# Ref_Volt.net
KiCad netlist of a schematic drawn in Altium Designer
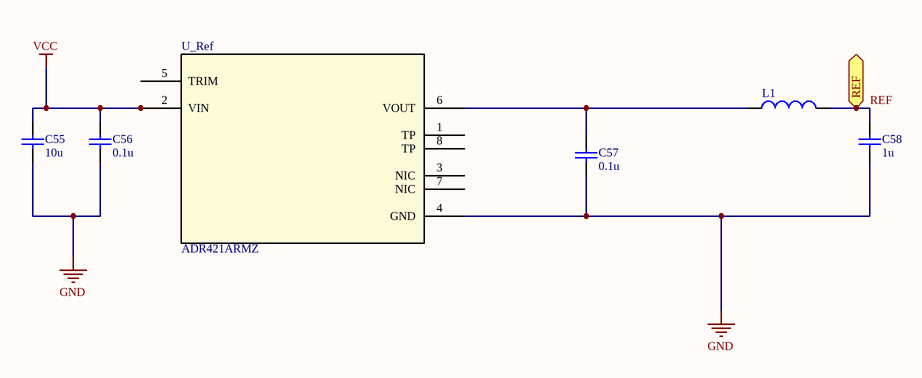
[diagram p0: Ref Volt.SchDoc]

(export (version "E")
  (design (tool "Eeschema 10.0.6"))
  (components
    (comp (ref "C55")
      (value "10u")
      (footprint "0805")
      (description "Ceramic Chip Capacitor - Standard")
      (fields (field (name "Comment") "C0805") (field (name "PUBLISHER") "Altium Limited"))
      (libsource (lib "KEMET Chip Capacitor") (part "C0805"))
    )
    (comp (ref "C56")
      (value "0.1u")
      (footprint "0603")
      (description "Ceramic Chip Capacitor - Standard")
      (fields (field (name "Comment") "C0603") (field (name "PUBLISHER") "Altium Limited"))
      (libsource (lib "KEMET Chip Capacitor") (part "C0603"))
    )
    (comp (ref "C57")
      (value "0.1u")
      (footprint "0603")
      (description "Ceramic Chip Capacitor - Standard")
      (fields (field (name "Comment") "C0603") (field (name "PUBLISHER") "Altium Limited"))
      (libsource (lib "KEMET Chip Capacitor") (part "C0603"))
    )
    (comp (ref "C58")
      (value "1u")
      (footprint "0805")
      (description "Ceramic Chip Capacitor - Standard")
      (fields (field (name "Comment") "C0805") (field (name "PUBLISHER") "Altium Limited"))
      (libsource (lib "KEMET Chip Capacitor") (part "C0805"))
    )
    (comp (ref "L1")
      (value "Inductor")
      (footprint "INDC1608L")
      (fields (field (name "PUBLISHER") "Altium Limited"))
      (libsource (lib "Miscellaneous Devices") (part "Inductor"))
    )
    (comp (ref "U_Ref")
      (value "ADR421ARMZ")
      (footprint "RM_8")
      (description "Imported")
      (libsource (lib "2016-11-05_23-52-08") (part "ADR421ARMZ"))
    )
  )
  (nets
    (net (code "1") (name "/REF") (class "Default")
      (node (ref "C58") (pin "1") (pinfunction "1_1") (pintype "passive"))
      (node (ref "L1") (pin "2") (pinfunction "2_2") (pintype "passive"))
    )
    (net (code "2") (name "GND") (class "Default")
      (node (ref "C55") (pin "1") (pinfunction "1_1") (pintype "passive"))
      (node (ref "C56") (pin "1") (pinfunction "1_1") (pintype "passive"))
      (node (ref "C57") (pin "1") (pinfunction "1_1") (pintype "passive"))
      (node (ref "C58") (pin "2") (pinfunction "2_2") (pintype "passive"))
      (node (ref "U_Ref") (pin "4") (pinfunction "GND_4") (pintype "passive"))
    )
    (net (code "3") (name "Net-(U_Ref-VOUT)") (class "Default")
      (node (ref "C57") (pin "2") (pinfunction "2_2") (pintype "passive"))
      (node (ref "L1") (pin "1") (pinfunction "1_1") (pintype "passive"))
      (node (ref "U_Ref") (pin "6") (pinfunction "VOUT_6") (pintype "passive"))
    )
    (net (code "4") (name "VCC") (class "Default")
      (node (ref "C55") (pin "2") (pinfunction "2_2") (pintype "passive"))
      (node (ref "C56") (pin "2") (pinfunction "2_2") (pintype "passive"))
      (node (ref "U_Ref") (pin "2") (pinfunction "VIN_2") (pintype "passive"))
    )
    (net (code "5") (name "unconnected-(U_Ref-NIC-Pad3)") (class "Default")
      (node (ref "U_Ref") (pin "3") (pinfunction "NIC_3") (pintype "passive"))
    )
    (net (code "6") (name "unconnected-(U_Ref-NIC-Pad7)") (class "Default")
      (node (ref "U_Ref") (pin "7") (pinfunction "NIC_7") (pintype "passive"))
    )
    (net (code "7") (name "unconnected-(U_Ref-TP-Pad1)") (class "Default")
      (node (ref "U_Ref") (pin "1") (pinfunction "TP_1") (pintype "passive"))
    )
    (net (code "8") (name "unconnected-(U_Ref-TP-Pad8)") (class "Default")
      (node (ref "U_Ref") (pin "8") (pinfunction "TP_8") (pintype "passive"))
    )
    (net (code "9") (name "unconnected-(U_Ref-TRIM-Pad5)") (class "Default")
      (node (ref "U_Ref") (pin "5") (pinfunction "TRIM_5") (pintype "passive"))
    )
  )
)
